# LG_TRACKER_DO.net
KiCad netlist of a schematic drawn in Altium Designer
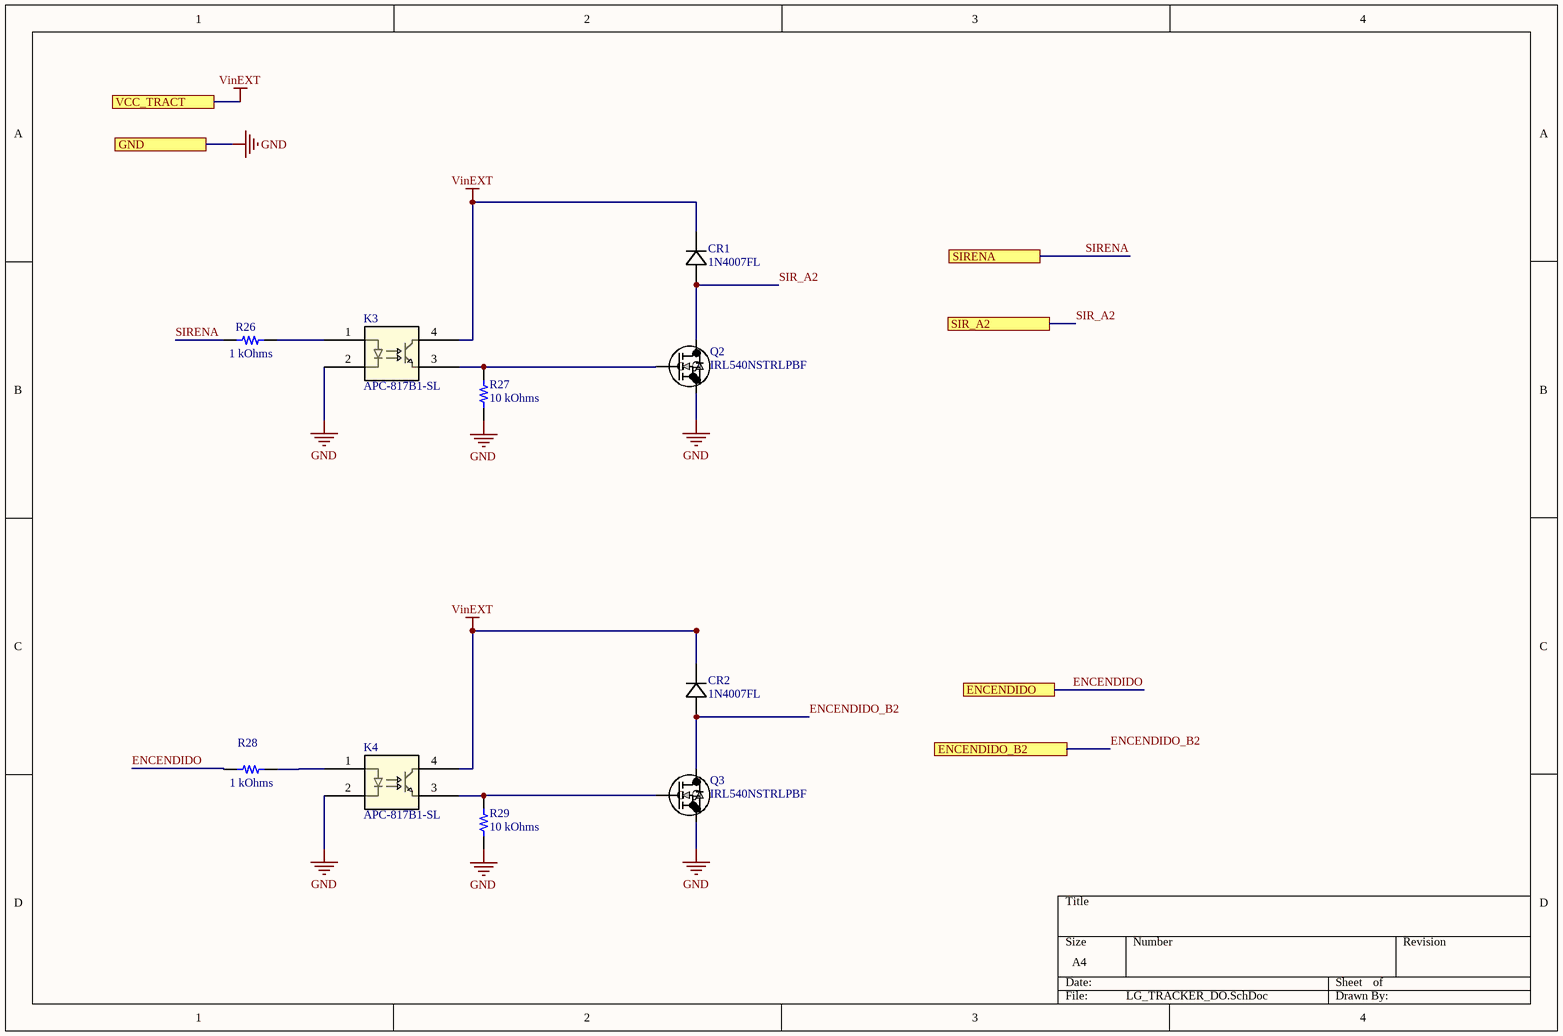
[diagram p0: LG_TRACKER_DO.SchDoc]

(export (version "E")
  (design (tool "Eeschema 10.0.6"))
  (components
    (comp (ref "CR1")
      (value "1N4007FL")
      (footprint "CR_SOD-123FL_SME")
      (description "Description")
      (fields (field (name "COPYRIGHT") "Copyright (C) 2025 Ultra Librarian. All rights reserved."))
      (libsource (lib "1N4007FL") (part "1N4007FL"))
    )
    (comp (ref "CR2")
      (value "1N4007FL")
      (footprint "CR_SOD-123FL_SME")
      (description "Description")
      (fields (field (name "COPYRIGHT") "Copyright (C) 2025 Ultra Librarian. All rights reserved."))
      (libsource (lib "1N4007FL") (part "1N4007FL"))
    )
    (comp (ref "K3")
      (value "APC-817B1-SL")
      (footprint "APC-817xx-SL_AMB")
      (description "Description")
      (fields (field (name "COPYRIGHT") "Copyright (C) 2025 Ultra Librarian. All rights reserved."))
      (libsource (lib "APC-817B1-SL") (part "APC-817B1-SL"))
    )
    (comp (ref "K4")
      (value "APC-817B1-SL")
      (footprint "APC-817xx-SL_AMB")
      (description "Description")
      (fields (field (name "COPYRIGHT") "Copyright (C) 2025 Ultra Librarian. All rights reserved."))
      (libsource (lib "APC-817B1-SL") (part "APC-817B1-SL"))
    )
    (comp (ref "Q2")
      (value "IRL540NSTRLPBF")
      (footprint "NMOSGSD_D2PAK_IRL540NSTRLPBF_INF")
      (description "Description")
      (fields (field (name "COPYRIGHT") "Copyright (C) 2025 Ultra Librarian. All rights reserved."))
      (libsource (lib "IRL540NSTRLPBF") (part "IRL540NSTRLPBF"))
    )
    (comp (ref "Q3")
      (value "IRL540NSTRLPBF")
      (footprint "NMOSGSD_D2PAK_IRL540NSTRLPBF_INF")
      (description "Description")
      (fields (field (name "COPYRIGHT") "Copyright (C) 2025 Ultra Librarian. All rights reserved."))
      (libsource (lib "IRL540NSTRLPBF") (part "IRL540NSTRLPBF"))
    )
    (comp (ref "R26")
      (value "1 kOhms")
      (footprint "RES 0402_1005")
      (description "RES SMD 1K OHM 0.1% 1/16W 0402")
      (fields (field (name "PART NUMBER") "AT0402BRD071KL") (field (name "MANUFACTURER") "Yageo"))
      (libsource (lib "Celestial Altium Library - altium_library") (part "Resistor"))
    )
    (comp (ref "R27")
      (value "10 kOhms")
      (footprint "RES 0603_1608")
      (description "RES 10K OHM 1% 1/10W 0603")
      (fields (field (name "PART NUMBER") "RC0603FR-0710KL") (field (name "MANUFACTURER") "Yageo"))
      (libsource (lib "Celestial Altium Library - altium_library") (part "Resistor"))
    )
    (comp (ref "R28")
      (value "1 kOhms")
      (footprint "RES 0402_1005")
      (description "RES SMD 1K OHM 0.1% 1/16W 0402")
      (fields (field (name "PART NUMBER") "AT0402BRD071KL") (field (name "MANUFACTURER") "Yageo"))
      (libsource (lib "Celestial Altium Library - altium_library") (part "Resistor"))
    )
    (comp (ref "R29")
      (value "10 kOhms")
      (footprint "RES 0603_1608")
      (description "RES 10K OHM 1% 1/10W 0603")
      (fields (field (name "PART NUMBER") "RC0603FR-0710KL") (field (name "MANUFACTURER") "Yageo"))
      (libsource (lib "Celestial Altium Library - altium_library") (part "Resistor"))
    )
  )
  (nets
    (net (code "1") (name "/ENCENDIDO") (class "Default")
      (node (ref "R28") (pin "1") (pinfunction "1_1") (pintype "passive"))
    )
    (net (code "2") (name "/ENCENDIDO_B2") (class "Default")
      (node (ref "CR2") (pin "2") (pinfunction "ANODE_2") (pintype "passive"))
      (node (ref "Q3") (pin "3") (pinfunction "D_3") (pintype "passive"))
    )
    (net (code "3") (name "/SIRENA") (class "Default")
      (node (ref "R26") (pin "1") (pinfunction "1_1") (pintype "passive"))
    )
    (net (code "4") (name "/SIR_A2") (class "Default")
      (node (ref "CR1") (pin "2") (pinfunction "ANODE_2") (pintype "passive"))
      (node (ref "Q2") (pin "3") (pinfunction "D_3") (pintype "passive"))
    )
    (net (code "5") (name "GND") (class "Default")
      (node (ref "K3") (pin "2") (pinfunction "2_2") (pintype "passive"))
      (node (ref "K4") (pin "2") (pinfunction "2_2") (pintype "passive"))
      (node (ref "Q2") (pin "2") (pinfunction "S_2") (pintype "passive"))
      (node (ref "Q3") (pin "2") (pinfunction "S_2") (pintype "passive"))
      (node (ref "R27") (pin "1") (pinfunction "1_1") (pintype "passive"))
      (node (ref "R29") (pin "1") (pinfunction "1_1") (pintype "passive"))
    )
    (net (code "6") (name "Net-(K3-Pad1)") (class "Default")
      (node (ref "K3") (pin "1") (pinfunction "1_1") (pintype "passive"))
      (node (ref "R26") (pin "2") (pinfunction "2_2") (pintype "passive"))
    )
    (net (code "7") (name "Net-(K4-Pad1)") (class "Default")
      (node (ref "K4") (pin "1") (pinfunction "1_1") (pintype "passive"))
      (node (ref "R28") (pin "2") (pinfunction "2_2") (pintype "passive"))
    )
    (net (code "8") (name "Net-(Q2-G)") (class "Default")
      (node (ref "K3") (pin "3") (pinfunction "3_3") (pintype "passive"))
      (node (ref "Q2") (pin "1") (pinfunction "G_1") (pintype "passive"))
      (node (ref "R27") (pin "2") (pinfunction "2_2") (pintype "passive"))
    )
    (net (code "9") (name "Net-(Q3-G)") (class "Default")
      (node (ref "K4") (pin "3") (pinfunction "3_3") (pintype "passive"))
      (node (ref "Q3") (pin "1") (pinfunction "G_1") (pintype "passive"))
      (node (ref "R29") (pin "2") (pinfunction "2_2") (pintype "passive"))
    )
    (net (code "10") (name "VinEXT") (class "Default")
      (node (ref "CR1") (pin "1") (pinfunction "CATHODE_1") (pintype "passive"))
      (node (ref "CR2") (pin "1") (pinfunction "CATHODE_1") (pintype "passive"))
      (node (ref "K3") (pin "4") (pinfunction "4_4") (pintype "passive"))
      (node (ref "K4") (pin "4") (pinfunction "4_4") (pintype "passive"))
    )
  )
)
